# BubbleSchem.net
KiCad netlist of a schematic drawn in Altium Designer
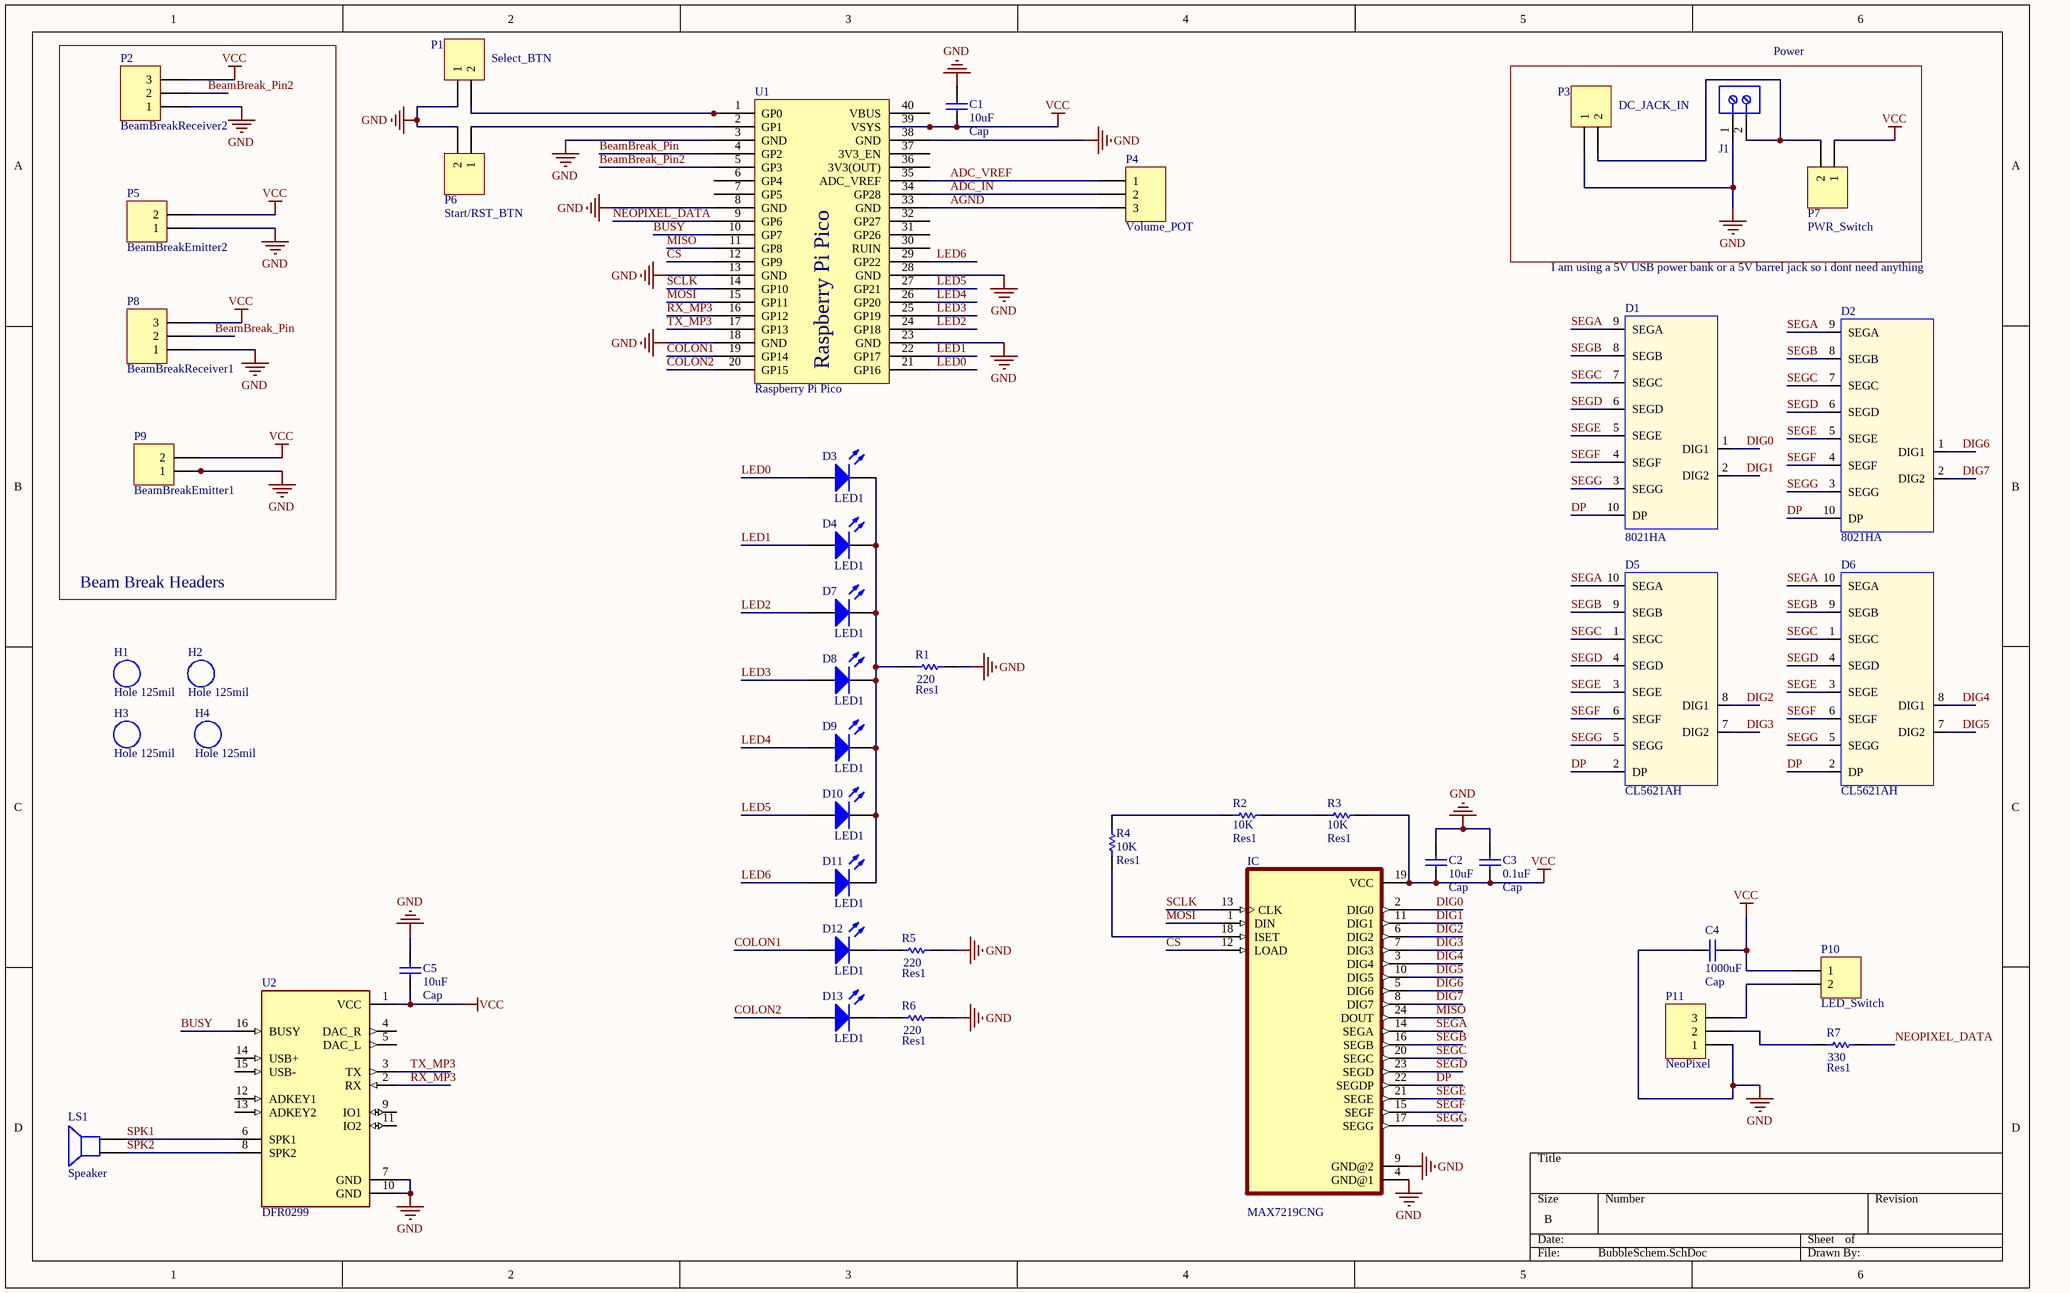
[diagram p0: BubbleSchem.SchDoc]

(export (version "E")
  (design (tool "Eeschema 10.0.6"))
  (components
    (comp (ref "C1")
      (value "Cap")
      (footprint "RAD-0.3")
      (description "Capacitor")
      (fields (field (name "ALTIUM_VALUE") "10uF") (field (name "PUBLISHER") "Altium Limited"))
      (libsource (lib "Miscellaneous Devices") (part "Cap"))
    )
    (comp (ref "C2")
      (value "Cap")
      (footprint "RAD-0.3")
      (description "Capacitor")
      (fields (field (name "ALTIUM_VALUE") "10uF") (field (name "PUBLISHER") "Altium Limited"))
      (libsource (lib "Miscellaneous Devices") (part "Cap"))
    )
    (comp (ref "C3")
      (value "Cap")
      (footprint "RAD-0.3")
      (description "Capacitor")
      (fields (field (name "ALTIUM_VALUE") "0.1uF") (field (name "PUBLISHER") "Altium Limited"))
      (libsource (lib "Miscellaneous Devices") (part "Cap"))
    )
    (comp (ref "C4")
      (value "Cap")
      (footprint "RAD-0.3")
      (description "Capacitor")
      (fields (field (name "ALTIUM_VALUE") "1000uF") (field (name "PUBLISHER") "Altium Limited"))
      (libsource (lib "Miscellaneous Devices") (part "Cap"))
    )
    (comp (ref "C5")
      (value "Cap")
      (footprint "RAD-0.3")
      (description "Capacitor")
      (fields (field (name "ALTIUM_VALUE") "10uF") (field (name "PUBLISHER") "Altium Limited"))
      (libsource (lib "Miscellaneous Devices") (part "Cap"))
    )
    (comp (ref "D1")
      (value "8021HA")
      (footprint "PCBComponent_1")
      (description "8021AH 7 Segment Display\r\n1.41\"x1.02x0.39\r\n35.8x25.8x14mm")
      (libsource (lib "8021AH") (part "8021HA"))
    )
    (comp (ref "D2")
      (value "8021HA")
      (footprint "PCBComponent_1")
      (description "8021AH 7 Segment Display\r\n1.41\"x1.02x0.39\r\n35.8x25.8x14mm")
      (libsource (lib "8021AH") (part "8021HA"))
    )
    (comp (ref "D3")
      (value "LED1")
      (footprint "LED")
      (description "Typical RED GaAs LED")
      (fields (field (name "PUBLISHER") "Altium Limited"))
      (libsource (lib "Miscellaneous Devices") (part "LED1"))
    )
    (comp (ref "D4")
      (value "LED1")
      (footprint "LED")
      (description "Typical RED GaAs LED")
      (fields (field (name "PUBLISHER") "Altium Limited"))
      (libsource (lib "Miscellaneous Devices") (part "LED1"))
    )
    (comp (ref "D5")
      (value "CL5621AH")
      (footprint "CL5621AH")
      (description "7 Segment Display 0.56\"\r\nCase size 25mmx19x8")
      (fields (field (name "MANUFACTURER") "XLITX TECHNOLOGY"))
      (libsource (lib "CL5621AH") (part "CL5621AH"))
    )
    (comp (ref "D6")
      (value "CL5621AH")
      (footprint "CL5621AH")
      (description "7 Segment Display 0.56\"\r\nCase size 25mmx19x8")
      (fields (field (name "MANUFACTURER") "XLITX TECHNOLOGY"))
      (libsource (lib "CL5621AH") (part "CL5621AH"))
    )
    (comp (ref "D7")
      (value "LED1")
      (footprint "LED")
      (description "Typical RED GaAs LED")
      (fields (field (name "PUBLISHER") "Altium Limited"))
      (libsource (lib "Miscellaneous Devices") (part "LED1"))
    )
    (comp (ref "D8")
      (value "LED1")
      (footprint "LED")
      (description "Typical RED GaAs LED")
      (fields (field (name "PUBLISHER") "Altium Limited"))
      (libsource (lib "Miscellaneous Devices") (part "LED1"))
    )
    (comp (ref "D9")
      (value "LED1")
      (footprint "LED")
      (description "Typical RED GaAs LED")
      (fields (field (name "PUBLISHER") "Altium Limited"))
      (libsource (lib "Miscellaneous Devices") (part "LED1"))
    )
    (comp (ref "D10")
      (value "LED1")
      (footprint "LED")
      (description "Typical RED GaAs LED")
      (fields (field (name "PUBLISHER") "Altium Limited"))
      (libsource (lib "Miscellaneous Devices") (part "LED1"))
    )
    (comp (ref "D11")
      (value "LED1")
      (footprint "LED")
      (description "Typical RED GaAs LED")
      (fields (field (name "PUBLISHER") "Altium Limited"))
      (libsource (lib "Miscellaneous Devices") (part "LED1"))
    )
    (comp (ref "D12")
      (value "LED1")
      (footprint "LED")
      (description "Typical RED GaAs LED")
      (fields (field (name "PUBLISHER") "Altium Limited"))
      (libsource (lib "Miscellaneous Devices") (part "LED1"))
    )
    (comp (ref "D13")
      (value "LED1")
      (footprint "LED")
      (description "Typical RED GaAs LED")
      (fields (field (name "PUBLISHER") "Altium Limited"))
      (libsource (lib "Miscellaneous Devices") (part "LED1"))
    )
    (comp (ref "H1")
      (value "Hole 125mil")
      (footprint "Hole 125mil")
      (libsource (lib "ECE Lib 22") (part "Hole 125mil"))
    )
    (comp (ref "H2")
      (value "Hole 125mil")
      (footprint "Hole 125mil")
      (libsource (lib "ECE Lib 22") (part "Hole 125mil"))
    )
    (comp (ref "H3")
      (value "Hole 125mil")
      (footprint "Hole 125mil")
      (libsource (lib "ECE Lib 22") (part "Hole 125mil"))
    )
    (comp (ref "H4")
      (value "Hole 125mil")
      (footprint "Hole 125mil")
      (libsource (lib "ECE Lib 22") (part "Hole 125mil"))
    )
    (comp (ref "IC")
      (value "MAX7219CNG")
      (footprint "DIP794W47P254L3213H457Q24")
      (description "IC DRVR 7 SEGMENT 8 DIGIT 24DIP")
      (fields (field (name "MF") "Maxim Integrated"))
      (libsource (lib "MAX7219CNG") (part "MAX7219CNG"))
    )
    (comp (ref "J1")
      (value "691137710002")
      (footprint "691137710002")
      (description "WR-TBL Series 1377 Horizontal Entry, THT, pitch 5mm, 2p")
      (fields (field (name "MANUFACTURER") "Wurth Elektronik"))
      (libsource (lib "Altium_WR-TBL_rev23f") (part "691137710002"))
    )
    (comp (ref "LS1")
      (value "Speaker")
      (footprint "PIN2")
      (description "Loudspeaker")
      (fields (field (name "PUBLISHER") "Altium Limited"))
      (libsource (lib "Miscellaneous Devices") (part "Speaker"))
    )
    (comp (ref "P1")
      (value "Select_BTN")
      (footprint "HDR1X2")
      (description "Header, 2-Pin, Right Angle")
      (fields (field (name "PUBLISHER") "Altium Limited"))
      (libsource (lib "") (part "Header 2H_2"))
    )
    (comp (ref "P2")
      (value "BeamBreakReceiver2")
      (footprint "HDR1X3")
      (description "Header, 3-Pin")
      (fields (field (name "PUBLISHER") "Altium Limited"))
      (libsource (lib "") (part "Header 3_1"))
    )
    (comp (ref "P3")
      (value "DC_JACK_IN")
      (footprint "HDR1X2")
      (description "Header, 2-Pin, Right Angle")
      (fields (field (name "PUBLISHER") "Altium Limited"))
      (libsource (lib "") (part "Header 2H_2"))
    )
    (comp (ref "P4")
      (value "Volume_POT")
      (footprint "HDR1X3")
      (description "Header, 3-Pin")
      (fields (field (name "PUBLISHER") "Altium Limited"))
      (libsource (lib "Miscellaneous Connectors") (part "Header 3"))
    )
    (comp (ref "P5")
      (value "BeamBreakEmitter2")
      (footprint "HDR1X2")
      (description "Header, 2-Pin, Right Angle")
      (fields (field (name "PUBLISHER") "Altium Limited"))
      (libsource (lib "Miscellaneous Connectors") (part "Header 2H"))
    )
    (comp (ref "P6")
      (value "Start/RST_BTN")
      (footprint "HDR1X2")
      (description "Header, 2-Pin, Right Angle")
      (fields (field (name "PUBLISHER") "Altium Limited"))
      (libsource (lib "") (part "Header 2H_1"))
    )
    (comp (ref "P7")
      (value "PWR_Switch")
      (footprint "HDR1X2")
      (description "Header, 2-Pin, Right Angle")
      (fields (field (name "PUBLISHER") "Altium Limited"))
      (libsource (lib "") (part "Header 2H_1"))
    )
    (comp (ref "P8")
      (value "BeamBreakReceiver1")
      (footprint "HDR1X3")
      (description "Header, 3-Pin")
      (fields (field (name "PUBLISHER") "Altium Limited"))
      (libsource (lib "") (part "Header 3_1"))
    )
    (comp (ref "P9")
      (value "BeamBreakEmitter1")
      (footprint "HDR1X2")
      (description "Header, 2-Pin, Right Angle")
      (fields (field (name "PUBLISHER") "Altium Limited"))
      (libsource (lib "Miscellaneous Connectors") (part "Header 2H"))
    )
    (comp (ref "P10")
      (value "LED_Switch")
      (footprint "HDR1X2")
      (description "Header, 2-Pin, Right Angle")
      (fields (field (name "PUBLISHER") "Altium Limited"))
      (libsource (lib "") (part "Header 2H_3"))
    )
    (comp (ref "P11")
      (value "NeoPixel")
      (footprint "HDR1X3")
      (description "Header, 3-Pin")
      (fields (field (name "PUBLISHER") "Altium Limited"))
      (libsource (lib "") (part "Header 3_1"))
    )
    (comp (ref "R1")
      (value "Res1")
      (footprint "AXIAL-0.3")
      (description "Resistor")
      (fields (field (name "ALTIUM_VALUE") "220") (field (name "PUBLISHER") "Altium Limited"))
      (libsource (lib "Miscellaneous Devices") (part "Res1"))
    )
    (comp (ref "R2")
      (value "Res1")
      (footprint "AXIAL-0.3")
      (description "Resistor")
      (fields (field (name "ALTIUM_VALUE") "10K") (field (name "PUBLISHER") "Altium Limited"))
      (libsource (lib "Miscellaneous Devices") (part "Res1"))
    )
    (comp (ref "R3")
      (value "Res1")
      (footprint "AXIAL-0.3")
      (description "Resistor")
      (fields (field (name "ALTIUM_VALUE") "10K") (field (name "PUBLISHER") "Altium Limited"))
      (libsource (lib "Miscellaneous Devices") (part "Res1"))
    )
    (comp (ref "R4")
      (value "Res1")
      (footprint "AXIAL-0.3")
      (description "Resistor")
      (fields (field (name "ALTIUM_VALUE") "10K") (field (name "PUBLISHER") "Altium Limited"))
      (libsource (lib "Miscellaneous Devices") (part "Res1"))
    )
    (comp (ref "R5")
      (value "Res1")
      (footprint "AXIAL-0.3")
      (description "Resistor")
      (fields (field (name "ALTIUM_VALUE") "220") (field (name "PUBLISHER") "Altium Limited"))
      (libsource (lib "Miscellaneous Devices") (part "Res1"))
    )
    (comp (ref "R6")
      (value "Res1")
      (footprint "AXIAL-0.3")
      (description "Resistor")
      (fields (field (name "ALTIUM_VALUE") "220") (field (name "PUBLISHER") "Altium Limited"))
      (libsource (lib "Miscellaneous Devices") (part "Res1"))
    )
    (comp (ref "R7")
      (value "Res1")
      (footprint "AXIAL-0.3")
      (description "Resistor")
      (fields (field (name "ALTIUM_VALUE") "330") (field (name "PUBLISHER") "Altium Limited"))
      (libsource (lib "Miscellaneous Devices") (part "Res1"))
    )
    (comp (ref "U1")
      (value "Raspberry Pi Pico")
      (footprint "Raspberry Pi Pico")
      (libsource (lib "ECE Lib 22") (part "Raspberry Pi Pico"))
    )
    (comp (ref "U2")
      (value "DFR0299")
      (footprint "MODULE_DFR0299")
      (description "- MP3 Player Audio Arduino Platform Evaluation Expansion Board")
      (fields (field (name "MF") "DFRobot"))
      (libsource (lib "DFR0299") (part "DFR0299"))
    )
  )
  (nets
    (net (code "1") (name "/ADC_IN") (class "Default")
      (node (ref "P4") (pin "2") (pinfunction "2_2") (pintype "passive"))
      (node (ref "U1") (pin "34") (pinfunction "GP28_34") (pintype "passive"))
    )
    (net (code "2") (name "/ADC_VREF") (class "Default")
      (node (ref "P4") (pin "1") (pinfunction "1_1") (pintype "passive"))
      (node (ref "U1") (pin "35") (pinfunction "ADC_VREF_35") (pintype "passive"))
    )
    (net (code "3") (name "/AGND") (class "Default")
      (node (ref "P4") (pin "3") (pinfunction "3_3") (pintype "passive"))
      (node (ref "U1") (pin "33") (pinfunction "GND_33") (pintype "passive"))
    )
    (net (code "4") (name "/BUSY") (class "Default")
      (node (ref "U1") (pin "10") (pinfunction "GP7_10") (pintype "passive"))
      (node (ref "U2") (pin "16") (pinfunction "BUSY_16") (pintype "input"))
    )
    (net (code "5") (name "/BeamBreak_Pin") (class "Default")
      (node (ref "P8") (pin "2") (pinfunction "2_2") (pintype "passive"))
      (node (ref "U1") (pin "4") (pinfunction "GP2_4") (pintype "passive"))
    )
    (net (code "6") (name "/BeamBreak_Pin2") (class "Default")
      (node (ref "P2") (pin "2") (pinfunction "2_2") (pintype "passive"))
      (node (ref "U1") (pin "5") (pinfunction "GP3_5") (pintype "passive"))
    )
    (net (code "7") (name "/COLON1") (class "Default")
      (node (ref "D12") (pin "1") (pinfunction "A_1") (pintype "passive"))
      (node (ref "U1") (pin "19") (pinfunction "GP14_19") (pintype "passive"))
    )
    (net (code "8") (name "/COLON2") (class "Default")
      (node (ref "D13") (pin "1") (pinfunction "A_1") (pintype "passive"))
      (node (ref "U1") (pin "20") (pinfunction "GP15_20") (pintype "passive"))
    )
    (net (code "9") (name "/CS") (class "Default")
      (node (ref "IC") (pin "12") (pinfunction "LOAD_12") (pintype "input"))
      (node (ref "U1") (pin "12") (pinfunction "GP9_12") (pintype "passive"))
    )
    (net (code "10") (name "/DIG0") (class "Default")
      (node (ref "D1") (pin "1") (pinfunction "DIG1_1") (pintype "passive"))
      (node (ref "IC") (pin "2") (pinfunction "DIG0_2") (pintype "output"))
    )
    (net (code "11") (name "/DIG1") (class "Default")
      (node (ref "D1") (pin "2") (pinfunction "DIG2_2") (pintype "passive"))
      (node (ref "IC") (pin "11") (pinfunction "DIG1_11") (pintype "output"))
    )
    (net (code "12") (name "/DIG2") (class "Default")
      (node (ref "D5") (pin "8") (pinfunction "DIG1_8") (pintype "passive"))
      (node (ref "IC") (pin "6") (pinfunction "DIG2_6") (pintype "output"))
    )
    (net (code "13") (name "/DIG3") (class "Default")
      (node (ref "D5") (pin "7") (pinfunction "DIG2_7") (pintype "passive"))
      (node (ref "IC") (pin "7") (pinfunction "DIG3_7") (pintype "output"))
    )
    (net (code "14") (name "/DIG4") (class "Default")
      (node (ref "D6") (pin "8") (pinfunction "DIG1_8") (pintype "passive"))
      (node (ref "IC") (pin "3") (pinfunction "DIG4_3") (pintype "output"))
    )
    (net (code "15") (name "/DIG5") (class "Default")
      (node (ref "D6") (pin "7") (pinfunction "DIG2_7") (pintype "passive"))
      (node (ref "IC") (pin "10") (pinfunction "DIG5_10") (pintype "output"))
    )
    (net (code "16") (name "/DIG6") (class "Default")
      (node (ref "D2") (pin "1") (pinfunction "DIG1_1") (pintype "passive"))
      (node (ref "IC") (pin "5") (pinfunction "DIG6_5") (pintype "output"))
    )
    (net (code "17") (name "/DIG7") (class "Default")
      (node (ref "D2") (pin "2") (pinfunction "DIG2_2") (pintype "passive"))
      (node (ref "IC") (pin "8") (pinfunction "DIG7_8") (pintype "output"))
    )
    (net (code "18") (name "/DP") (class "Default")
      (node (ref "D1") (pin "10") (pinfunction "DP_10") (pintype "passive"))
      (node (ref "D2") (pin "10") (pinfunction "DP_10") (pintype "passive"))
      (node (ref "D5") (pin "2") (pinfunction "DP_2") (pintype "passive"))
      (node (ref "D6") (pin "2") (pinfunction "DP_2") (pintype "passive"))
      (node (ref "IC") (pin "22") (pinfunction "SEGDP_22") (pintype "output"))
    )
    (net (code "19") (name "/LED0") (class "Default")
      (node (ref "D3") (pin "1") (pinfunction "A_1") (pintype "passive"))
      (node (ref "U1") (pin "21") (pinfunction "GP16_21") (pintype "passive"))
    )
    (net (code "20") (name "/LED1") (class "Default")
      (node (ref "D4") (pin "1") (pinfunction "A_1") (pintype "passive"))
      (node (ref "U1") (pin "22") (pinfunction "GP17_22") (pintype "passive"))
    )
    (net (code "21") (name "/LED2") (class "Default")
      (node (ref "D7") (pin "1") (pinfunction "A_1") (pintype "passive"))
      (node (ref "U1") (pin "24") (pinfunction "GP18_24") (pintype "passive"))
    )
    (net (code "22") (name "/LED3") (class "Default")
      (node (ref "D8") (pin "1") (pinfunction "A_1") (pintype "passive"))
      (node (ref "U1") (pin "25") (pinfunction "GP19_25") (pintype "passive"))
    )
    (net (code "23") (name "/LED4") (class "Default")
      (node (ref "D9") (pin "1") (pinfunction "A_1") (pintype "passive"))
      (node (ref "U1") (pin "26") (pinfunction "GP20_26") (pintype "passive"))
    )
    (net (code "24") (name "/LED5") (class "Default")
      (node (ref "D10") (pin "1") (pinfunction "A_1") (pintype "passive"))
      (node (ref "U1") (pin "27") (pinfunction "GP21_27") (pintype "passive"))
    )
    (net (code "25") (name "/LED6") (class "Default")
      (node (ref "D11") (pin "1") (pinfunction "A_1") (pintype "passive"))
      (node (ref "U1") (pin "29") (pinfunction "GP22_29") (pintype "passive"))
    )
    (net (code "26") (name "/MISO") (class "Default")
      (node (ref "IC") (pin "24") (pinfunction "DOUT_24") (pintype "output"))
      (node (ref "U1") (pin "11") (pinfunction "GP8_11") (pintype "passive"))
    )
    (net (code "27") (name "/MOSI") (class "Default")
      (node (ref "IC") (pin "1") (pinfunction "DIN_1") (pintype "input"))
      (node (ref "U1") (pin "15") (pinfunction "GP11_15") (pintype "passive"))
    )
    (net (code "28") (name "/NEOPIXEL_DATA") (class "Default")
      (node (ref "R7") (pin "2") (pinfunction "2_2") (pintype "passive"))
      (node (ref "U1") (pin "9") (pinfunction "GP6_9") (pintype "passive"))
    )
    (net (code "29") (name "/RX_MP3") (class "Default")
      (node (ref "U1") (pin "16") (pinfunction "GP12_16") (pintype "passive"))
      (node (ref "U2") (pin "2") (pinfunction "RX_2") (pintype "input"))
    )
    (net (code "30") (name "/SCLK") (class "Default")
      (node (ref "IC") (pin "13") (pinfunction "CLK_13") (pintype "input"))
      (node (ref "U1") (pin "14") (pinfunction "GP10_14") (pintype "passive"))
    )
    (net (code "31") (name "/SEGA") (class "Default")
      (node (ref "D1") (pin "9") (pinfunction "SEGA_9") (pintype "passive"))
      (node (ref "D2") (pin "9") (pinfunction "SEGA_9") (pintype "passive"))
      (node (ref "D5") (pin "10") (pinfunction "SEGA_10") (pintype "passive"))
      (node (ref "D6") (pin "10") (pinfunction "SEGA_10") (pintype "passive"))
      (node (ref "IC") (pin "14") (pinfunction "SEGA_14") (pintype "output"))
    )
    (net (code "32") (name "/SEGB") (class "Default")
      (node (ref "D1") (pin "8") (pinfunction "SEGB_8") (pintype "passive"))
      (node (ref "D2") (pin "8") (pinfunction "SEGB_8") (pintype "passive"))
      (node (ref "D5") (pin "9") (pinfunction "SEGB_9") (pintype "passive"))
      (node (ref "D6") (pin "9") (pinfunction "SEGB_9") (pintype "passive"))
      (node (ref "IC") (pin "16") (pinfunction "SEGB_16") (pintype "output"))
    )
    (net (code "33") (name "/SEGC") (class "Default")
      (node (ref "D1") (pin "7") (pinfunction "SEGC_7") (pintype "passive"))
      (node (ref "D2") (pin "7") (pinfunction "SEGC_7") (pintype "passive"))
      (node (ref "D5") (pin "1") (pinfunction "SEGC_1") (pintype "passive"))
      (node (ref "D6") (pin "1") (pinfunction "SEGC_1") (pintype "passive"))
      (node (ref "IC") (pin "20") (pinfunction "SEGC_20") (pintype "output"))
    )
    (net (code "34") (name "/SEGD") (class "Default")
      (node (ref "D1") (pin "6") (pinfunction "SEGD_6") (pintype "passive"))
      (node (ref "D2") (pin "6") (pinfunction "SEGD_6") (pintype "passive"))
      (node (ref "D5") (pin "4") (pinfunction "SEGD_4") (pintype "passive"))
      (node (ref "D6") (pin "4") (pinfunction "SEGD_4") (pintype "passive"))
      (node (ref "IC") (pin "23") (pinfunction "SEGD_23") (pintype "output"))
    )
    (net (code "35") (name "/SEGE") (class "Default")
      (node (ref "D1") (pin "5") (pinfunction "SEGE_5") (pintype "passive"))
      (node (ref "D2") (pin "5") (pinfunction "SEGE_5") (pintype "passive"))
      (node (ref "D5") (pin "3") (pinfunction "SEGE_3") (pintype "passive"))
      (node (ref "D6") (pin "3") (pinfunction "SEGE_3") (pintype "passive"))
      (node (ref "IC") (pin "21") (pinfunction "SEGE_21") (pintype "output"))
    )
    (net (code "36") (name "/SEGF") (class "Default")
      (node (ref "D1") (pin "4") (pinfunction "SEGF_4") (pintype "passive"))
      (node (ref "D2") (pin "4") (pinfunction "SEGF_4") (pintype "passive"))
      (node (ref "D5") (pin "6") (pinfunction "SEGF_6") (pintype "passive"))
      (node (ref "D6") (pin "6") (pinfunction "SEGF_6") (pintype "passive"))
      (node (ref "IC") (pin "15") (pinfunction "SEGF_15") (pintype "output"))
    )
    (net (code "37") (name "/SEGG") (class "Default")
      (node (ref "D1") (pin "3") (pinfunction "SEGG_3") (pintype "passive"))
      (node (ref "D2") (pin "3") (pinfunction "SEGG_3") (pintype "passive"))
      (node (ref "D5") (pin "5") (pinfunction "SEGG_5") (pintype "passive"))
      (node (ref "D6") (pin "5") (pinfunction "SEGG_5") (pintype "passive"))
      (node (ref "IC") (pin "17") (pinfunction "SEGG_17") (pintype "output"))
    )
    (net (code "38") (name "/SPK1") (class "Default")
      (node (ref "LS1") (pin "2") (pinfunction "2_2") (pintype "passive"))
      (node (ref "U2") (pin "6") (pinfunction "SPK1_6") (pintype "passive"))
    )
    (net (code "39") (name "/SPK2") (class "Default")
      (node (ref "LS1") (pin "1") (pinfunction "1_1") (pintype "passive"))
      (node (ref "U2") (pin "8") (pinfunction "SPK2_8") (pintype "passive"))
    )
    (net (code "40") (name "/TX_MP3") (class "Default")
      (node (ref "U1") (pin "17") (pinfunction "GP13_17") (pintype "passive"))
      (node (ref "U2") (pin "3") (pinfunction "TX_3") (pintype "output"))
    )
    (net (code "41") (name "GND") (class "Default")
      (node (ref "C1") (pin "1") (pinfunction "1_1") (pintype "passive"))
      (node (ref "C2") (pin "2") (pinfunction "2_2") (pintype "passive"))
      (node (ref "C3") (pin "2") (pinfunction "2_2") (pintype "passive"))
      (node (ref "C4") (pin "2") (pinfunction "2_2") (pintype "passive"))
      (node (ref "C5") (pin "2") (pinfunction "2_2") (pintype "passive"))
      (node (ref "IC") (pin "4") (pinfunction "GND@1_4") (pintype "power_in"))
      (node (ref "IC") (pin "9") (pinfunction "GND@2_9") (pintype "power_in"))
      (node (ref "J1") (pin "1") (pinfunction "1_1") (pintype "passive"))
      (node (ref "P1") (pin "1") (pinfunction "1_1") (pintype "passive"))
      (node (ref "P11") (pin "1") (pinfunction "1_1") (pintype "passive"))
      (node (ref "P2") (pin "1") (pinfunction "1_1") (pintype "passive"))
      (node (ref "P3") (pin "1") (pinfunction "1_1") (pintype "passive"))
      (node (ref "P5") (pin "1") (pinfunction "1_1") (pintype "passive"))
      (node (ref "P6") (pin "2") (pinfunction "2_2") (pintype "passive"))
      (node (ref "P8") (pin "1") (pinfunction "1_1") (pintype "passive"))
      (node (ref "P9") (pin "1") (pinfunction "1_1") (pintype "passive"))
      (node (ref "R1") (pin "2") (pinfunction "2_2") (pintype "passive"))
      (node (ref "R5") (pin "2") (pinfunction "2_2") (pintype "passive"))
      (node (ref "R6") (pin "2") (pinfunction "2_2") (pintype "passive"))
      (node (ref "U1") (pin "13") (pinfunction "GND_13") (pintype "passive"))
      (node (ref "U1") (pin "18") (pinfunction "GND_18") (pintype "passive"))
      (node (ref "U1") (pin "23") (pinfunction "GND_23") (pintype "passive"))
      (node (ref "U1") (pin "28") (pinfunction "GND_28") (pintype "passive"))
      (node (ref "U1") (pin "3") (pinfunction "GND_3") (pintype "passive"))
      (node (ref "U1") (pin "38") (pinfunction "GND_38") (pintype "passive"))
      (node (ref "U1") (pin "8") (pinfunction "GND_8") (pintype "passive"))
      (node (ref "U2") (pin "10") (pinfunction "GND_10") (pintype "power_in"))
      (node (ref "U2") (pin "7") (pinfunction "GND_7") (pintype "power_in"))
    )
    (net (code "42") (name "Net-(D10-K)") (class "Default")
      (node (ref "D10") (pin "2") (pinfunction "K_2") (pintype "passive"))
      (node (ref "D11") (pin "2") (pinfunction "K_2") (pintype "passive"))
      (node (ref "D3") (pin "2") (pinfunction "K_2") (pintype "passive"))
      (node (ref "D4") (pin "2") (pinfunction "K_2") (pintype "passive"))
      (node (ref "D7") (pin "2") (pinfunction "K_2") (pintype "passive"))
      (node (ref "D8") (pin "2") (pinfunction "K_2") (pintype "passive"))
      (node (ref "D9") (pin "2") (pinfunction "K_2") (pintype "passive"))
      (node (ref "R1") (pin "1") (pinfunction "1_1") (pintype "passive"))
    )
    (net (code "43") (name "Net-(D12-K)") (class "Default")
      (node (ref "D12") (pin "2") (pinfunction "K_2") (pintype "passive"))
      (node (ref "R5") (pin "1") (pinfunction "1_1") (pintype "passive"))
    )
    (net (code "44") (name "Net-(D13-K)") (class "Default")
      (node (ref "D13") (pin "2") (pinfunction "K_2") (pintype "passive"))
      (node (ref "R6") (pin "1") (pinfunction "1_1") (pintype "passive"))
    )
    (net (code "45") (name "Net-(IC-ISET)") (class "Default")
      (node (ref "IC") (pin "18") (pinfunction "ISET_18") (pintype "input"))
      (node (ref "R4") (pin "1") (pinfunction "1_1") (pintype "passive"))
    )
    (net (code "46") (name "Net-(J1-Pad2)") (class "Default")
      (node (ref "J1") (pin "2") (pinfunction "2_2") (pintype "passive"))
      (node (ref "P3") (pin "2") (pinfunction "2_2") (pintype "passive"))
      (node (ref "P7") (pin "2") (pinfunction "2_2") (pintype "passive"))
    )
    (net (code "47") (name "Net-(P10-Pad2)") (class "Default")
      (node (ref "P10") (pin "2") (pinfunction "2_2") (pintype "passive"))
      (node (ref "P11") (pin "3") (pinfunction "3_3") (pintype "passive"))
    )
    (net (code "48") (name "Net-(P11-Pad2)") (class "Default")
      (node (ref "P11") (pin "2") (pinfunction "2_2") (pintype "passive"))
      (node (ref "R7") (pin "1") (pinfunction "1_1") (pintype "passive"))
    )
    (net (code "49") (name "Net-(R2-Pad1)") (class "Default")
      (node (ref "R2") (pin "1") (pinfunction "1_1") (pintype "passive"))
      (node (ref "R4") (pin "2") (pinfunction "2_2") (pintype "passive"))
    )
    (net (code "50") (name "Net-(R2-Pad2)") (class "Default")
      (node (ref "R2") (pin "2") (pinfunction "2_2") (pintype "passive"))
      (node (ref "R3") (pin "1") (pinfunction "1_1") (pintype "passive"))
    )
    (net (code "51") (name "Net-(U1-GP0)") (class "Default")
      (node (ref "P1") (pin "2") (pinfunction "2_2") (pintype "passive"))
      (node (ref "U1") (pin "1") (pinfunction "GP0_1") (pintype "passive"))
    )
    (net (code "52") (name "Net-(U1-GP1)") (class "Default")
      (node (ref "P6") (pin "1") (pinfunction "1_1") (pintype "passive"))
      (node (ref "U1") (pin "2") (pinfunction "GP1_2") (pintype "passive"))
    )
    (net (code "53") (name "VCC") (class "Default")
      (node (ref "C1") (pin "2") (pinfunction "2_2") (pintype "passive"))
      (node (ref "C2") (pin "1") (pinfunction "1_1") (pintype "passive"))
      (node (ref "C3") (pin "1") (pinfunction "1_1") (pintype "passive"))
      (node (ref "C4") (pin "1") (pinfunction "1_1") (pintype "passive"))
      (node (ref "C5") (pin "1") (pinfunction "1_1") (pintype "passive"))
      (node (ref "IC") (pin "19") (pinfunction "VCC_19") (pintype "power_in"))
      (node (ref "P10") (pin "1") (pinfunction "1_1") (pintype "passive"))
      (node (ref "P2") (pin "3") (pinfunction "3_3") (pintype "passive"))
      (node (ref "P5") (pin "2") (pinfunction "2_2") (pintype "passive"))
      (node (ref "P7") (pin "1") (pinfunction "1_1") (pintype "passive"))
      (node (ref "P8") (pin "3") (pinfunction "3_3") (pintype "passive"))
      (node (ref "P9") (pin "2") (pinfunction "2_2") (pintype "passive"))
      (node (ref "R3") (pin "2") (pinfunction "2_2") (pintype "passive"))
      (node (ref "U1") (pin "39") (pinfunction "VSYS_39") (pintype "passive"))
      (node (ref "U2") (pin "1") (pinfunction "VCC_1") (pintype "power_in"))
    )
    (net (code "54") (name "unconnected-(U1-3V3(OUT)-Pad36)") (class "Default")
      (node (ref "U1") (pin "36") (pinfunction "3V3(OUT)_36") (pintype "passive"))
    )
    (net (code "55") (name "unconnected-(U1-3V3_EN-Pad37)") (class "Default")
      (node (ref "U1") (pin "37") (pinfunction "3V3_EN_37") (pintype "passive"))
    )
    (net (code "56") (name "unconnected-(U1-GP4-Pad6)") (class "Default")
      (node (ref "U1") (pin "6") (pinfunction "GP4_6") (pintype "passive"))
    )
    (net (code "57") (name "unconnected-(U1-GP5-Pad7)") (class "Default")
      (node (ref "U1") (pin "7") (pinfunction "GP5_7") (pintype "passive"))
    )
    (net (code "58") (name "unconnected-(U1-GP26-Pad31)") (class "Default")
      (node (ref "U1") (pin "31") (pinfunction "GP26_31") (pintype "passive"))
    )
    (net (code "59") (name "unconnected-(U1-GP27-Pad32)") (class "Default")
      (node (ref "U1") (pin "32") (pinfunction "GP27_32") (pintype "passive"))
    )
    (net (code "60") (name "unconnected-(U1-RUIN-Pad30)") (class "Default")
      (node (ref "U1") (pin "30") (pinfunction "RUIN_30") (pintype "passive"))
    )
    (net (code "61") (name "unconnected-(U1-VBUS-Pad40)") (class "Default")
      (node (ref "U1") (pin "40") (pinfunction "VBUS_40") (pintype "passive"))
    )
    (net (code "62") (name "unconnected-(U2-ADKEY1-Pad12)") (class "Default")
      (node (ref "U2") (pin "12") (pinfunction "ADKEY1_12") (pintype "input"))
    )
    (net (code "63") (name "unconnected-(U2-ADKEY2-Pad13)") (class "Default")
      (node (ref "U2") (pin "13") (pinfunction "ADKEY2_13") (pintype "input"))
    )
    (net (code "64") (name "unconnected-(U2-DAC_L-Pad5)") (class "Default")
      (node (ref "U2") (pin "5") (pinfunction "DAC_L_5") (pintype "output"))
    )
    (net (code "65") (name "unconnected-(U2-DAC_R-Pad4)") (class "Default")
      (node (ref "U2") (pin "4") (pinfunction "DAC_R_4") (pintype "output"))
    )
    (net (code "66") (name "unconnected-(U2-IO1-Pad9)") (class "Default")
      (node (ref "U2") (pin "9") (pinfunction "IO1_9") (pintype "bidirectional"))
    )
    (net (code "67") (name "unconnected-(U2-IO2-Pad11)") (class "Default")
      (node (ref "U2") (pin "11") (pinfunction "IO2_11") (pintype "bidirectional"))
    )
    (net (code "68") (name "unconnected-(U2-USB+-Pad14)") (class "Default")
      (node (ref "U2") (pin "14") (pinfunction "USB+_14") (pintype "input"))
    )
    (net (code "69") (name "unconnected-(U2-USB--Pad15)") (class "Default")
      (node (ref "U2") (pin "15") (pinfunction "USB-_15") (pintype "input"))
    )
  )
)
